# Sheet1.net
KiCad netlist of a schematic drawn in Altium Designer
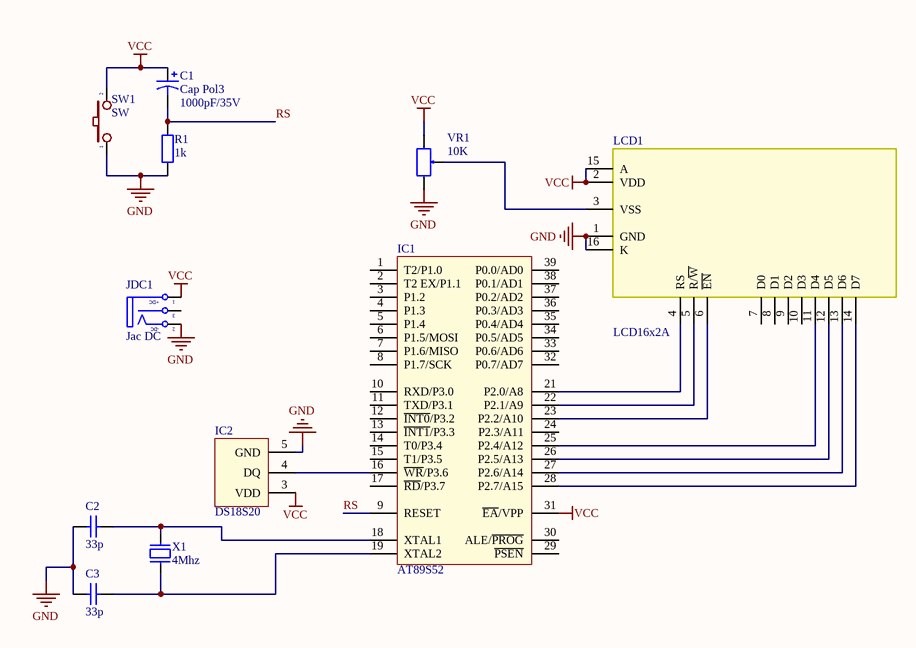
[diagram p0: Sheet1.SchDoc]

(export (version "E")
  (design (tool "Eeschema 10.0.6"))
  (components
    (comp (ref "C1")
      (value "Cap Pol3")
      (footprint "CP2/5")
      (description "Polarized Capacitor (Surface Mount)")
      (fields (field (name "ALTIUM_VALUE") "1000pF/35V") (field (name "PUBLISHER") "Altium Limited"))
      (libsource (lib "syhaunguyen") (part "Cap Pol3"))
    )
    (comp (ref "C2")
      (value "33p")
      (footprint "Tu-pico")
      (description "Capacitor")
      (fields (field (name "Comment") "Capacitor Ceramic") (field (name "PUBLISHER") "Altium Limited"))
      (libsource (lib "hphonglib") (part "CapCeramic"))
    )
    (comp (ref "C3")
      (value "33p")
      (footprint "Tu-pico")
      (description "Capacitor")
      (fields (field (name "Comment") "Capacitor Ceramic") (field (name "PUBLISHER") "Altium Limited"))
      (libsource (lib "hphonglib") (part "CapCeramic"))
    )
    (comp (ref "IC1")
      (value "AT89S52")
      (footprint "DIP40/W0.6")
      (description "AT89S52, 8k Byte Flash Memory , 40 Pin")
      (libsource (lib "syhaunguyen") (part "AT89S52"))
    )
    (comp (ref "IC2")
      (value "DS18S20")
      (footprint "DS18S20")
      (description "High Precision  1-Wire® Digital Thermometer")
      (libsource (lib "syhaunguyen") (part "DS18S20"))
    )
    (comp (ref "JDC1")
      (value "Jac DC")
      (footprint "DC-IN")
      (description "Jac DC input")
      (libsource (lib "syhaunguyen") (part "DCIN"))
    )
    (comp (ref "LCD1")
      (value "LCD16x2A")
      (footprint "LCD16X2")
      (description "LCD dipslay 16 char, 2 line")
      (libsource (lib "syhaunguyen") (part "LCD16x2"))
    )
    (comp (ref "R1")
      (value "1k")
      (footprint "R1/4W")
      (description "Resistor 1/4W")
      (libsource (lib "syhaunguyen") (part "R1/4W"))
    )
    (comp (ref "SW1")
      (value "SW")
      (footprint "SW2")
      (description "Switch button 2 pin")
      (libsource (lib "syhaunguyen") (part "SW2"))
    )
    (comp (ref "VR1")
      (value "10K")
      (footprint "VR")
      (description "Var Resistor")
      (libsource (lib "hphonglib") (part "VR"))
    )
    (comp (ref "X1")
      (value "4Mhz")
      (footprint "XT2")
      (description "Crystal For all Crystal 2pin.")
      (libsource (lib "hphonglib") (part "XT2"))
    )
  )
  (nets
    (net (code "1") (name "/RS") (class "Default")
      (node (ref "C1") (pin "2") (pinfunction "2_2") (pintype "passive"))
      (node (ref "IC1") (pin "9") (pinfunction "RESET_9") (pintype "passive"))
      (node (ref "R1") (pin "2") (pinfunction "2_2") (pintype "passive"))
    )
    (net (code "2") (name "GND") (class "Default")
      (node (ref "C2") (pin "1") (pinfunction "1_1") (pintype "passive"))
      (node (ref "C3") (pin "1") (pinfunction "1_1") (pintype "passive"))
      (node (ref "IC1") (pin "20") (pinfunction "GND_20") (pintype "power_in"))
      (node (ref "IC2") (pin "5") (pinfunction "GND_5") (pintype "passive"))
      (node (ref "JDC1") (pin "2") (pinfunction "TN_2") (pintype "passive"))
      (node (ref "LCD1") (pin "1") (pinfunction "GND_1") (pintype "passive"))
      (node (ref "LCD1") (pin "16") (pinfunction "K_16") (pintype "passive"))
      (node (ref "R1") (pin "1") (pinfunction "1_1") (pintype "passive"))
      (node (ref "SW1") (pin "1") (pinfunction "1_1") (pintype "passive"))
      (node (ref "VR1") (pin "3") (pinfunction "3_3") (pintype "passive"))
    )
    (net (code "3") (name "Net-(IC1-P2.0{slash}A8)") (class "Default")
      (node (ref "IC1") (pin "21") (pinfunction "P2.0/A8_21") (pintype "passive"))
      (node (ref "LCD1") (pin "4") (pinfunction "RS_4") (pintype "passive"))
    )
    (net (code "4") (name "Net-(IC1-P2.1{slash}A9)") (class "Default")
      (node (ref "IC1") (pin "22") (pinfunction "P2.1/A9_22") (pintype "passive"))
      (node (ref "LCD1") (pin "5") (pinfunction "R/~{W}_5") (pintype "passive"))
    )
    (net (code "5") (name "Net-(IC1-P2.2{slash}A10)") (class "Default")
      (node (ref "IC1") (pin "23") (pinfunction "P2.2/A10_23") (pintype "passive"))
      (node (ref "LCD1") (pin "6") (pinfunction "~{EN}_6") (pintype "passive"))
    )
    (net (code "6") (name "Net-(IC1-P2.4{slash}A12)") (class "Default")
      (node (ref "IC1") (pin "25") (pinfunction "P2.4/A12_25") (pintype "passive"))
      (node (ref "LCD1") (pin "11") (pinfunction "D4_11") (pintype "passive"))
    )
    (net (code "7") (name "Net-(IC1-P2.5{slash}A13)") (class "Default")
      (node (ref "IC1") (pin "26") (pinfunction "P2.5/A13_26") (pintype "passive"))
      (node (ref "LCD1") (pin "12") (pinfunction "D5_12") (pintype "passive"))
    )
    (net (code "8") (name "Net-(IC1-P2.6{slash}A14)") (class "Default")
      (node (ref "IC1") (pin "27") (pinfunction "P2.6/A14_27") (pintype "passive"))
      (node (ref "LCD1") (pin "13") (pinfunction "D6_13") (pintype "passive"))
    )
    (net (code "9") (name "Net-(IC1-P2.7{slash}A15)") (class "Default")
      (node (ref "IC1") (pin "28") (pinfunction "P2.7/A15_28") (pintype "passive"))
      (node (ref "LCD1") (pin "14") (pinfunction "D7_14") (pintype "passive"))
    )
    (net (code "10") (name "Net-(IC1-XTAL1)") (class "Default")
      (node (ref "C2") (pin "2") (pinfunction "2_2") (pintype "passive"))
      (node (ref "IC1") (pin "18") (pinfunction "XTAL1_18") (pintype "passive"))
      (node (ref "X1") (pin "1") (pinfunction "1_1") (pintype "passive"))
    )
    (net (code "11") (name "Net-(IC1-XTAL2)") (class "Default")
      (node (ref "C3") (pin "2") (pinfunction "2_2") (pintype "passive"))
      (node (ref "IC1") (pin "19") (pinfunction "XTAL2_19") (pintype "passive"))
      (node (ref "X1") (pin "2") (pinfunction "2_2") (pintype "passive"))
    )
    (net (code "12") (name "Net-(IC1-~{WR}{slash}P3.6)") (class "Default")
      (node (ref "IC1") (pin "16") (pinfunction "~{WR}/P3.6_16") (pintype "passive"))
      (node (ref "IC2") (pin "4") (pinfunction "DQ_4") (pintype "passive"))
    )
    (net (code "13") (name "Net-(LCD1-VSS)") (class "Default")
      (node (ref "LCD1") (pin "3") (pinfunction "VSS_3") (pintype "passive"))
      (node (ref "VR1") (pin "2") (pinfunction "2_2") (pintype "passive"))
    )
    (net (code "14") (name "VCC") (class "Default")
      (node (ref "C1") (pin "1") (pinfunction "1_1") (pintype "passive"))
      (node (ref "IC1") (pin "31") (pinfunction "~{EA}/VPP_31") (pintype "passive"))
      (node (ref "IC1") (pin "40") (pinfunction "VCC_40") (pintype "power_in"))
      (node (ref "IC2") (pin "3") (pinfunction "VDD_3") (pintype "passive"))
      (node (ref "JDC1") (pin "1") (pinfunction "T_1") (pintype "passive"))
      (node (ref "LCD1") (pin "15") (pinfunction "A_15") (pintype "passive"))
      (node (ref "LCD1") (pin "2") (pinfunction "VDD_2") (pintype "passive"))
      (node (ref "SW1") (pin "2") (pinfunction "2_2") (pintype "passive"))
      (node (ref "VR1") (pin "1") (pinfunction "1_1") (pintype "passive"))
    )
    (net (code "15") (name "unconnected-(IC1-ALE{slash}~{PROG}-Pad30)") (class "Default")
      (node (ref "IC1") (pin "30") (pinfunction "ALE/~{PROG}_30") (pintype "passive"))
    )
    (net (code "16") (name "unconnected-(IC1-P0.0{slash}AD0-Pad39)") (class "Default")
      (node (ref "IC1") (pin "39") (pinfunction "P0.0/AD0_39") (pintype "passive"))
    )
    (net (code "17") (name "unconnected-(IC1-P0.1{slash}AD1-Pad38)") (class "Default")
      (node (ref "IC1") (pin "38") (pinfunction "P0.1/AD1_38") (pintype "passive"))
    )
    (net (code "18") (name "unconnected-(IC1-P0.2{slash}AD2-Pad37)") (class "Default")
      (node (ref "IC1") (pin "37") (pinfunction "P0.2/AD2_37") (pintype "passive"))
    )
    (net (code "19") (name "unconnected-(IC1-P0.3{slash}AD3-Pad36)") (class "Default")
      (node (ref "IC1") (pin "36") (pinfunction "P0.3/AD3_36") (pintype "passive"))
    )
    (net (code "20") (name "unconnected-(IC1-P0.4{slash}AD4-Pad35)") (class "Default")
      (node (ref "IC1") (pin "35") (pinfunction "P0.4/AD4_35") (pintype "passive"))
    )
    (net (code "21") (name "unconnected-(IC1-P0.5{slash}AD5-Pad34)") (class "Default")
      (node (ref "IC1") (pin "34") (pinfunction "P0.5/AD5_34") (pintype "passive"))
    )
    (net (code "22") (name "unconnected-(IC1-P0.6{slash}AD6-Pad33)") (class "Default")
      (node (ref "IC1") (pin "33") (pinfunction "P0.6/AD6_33") (pintype "passive"))
    )
    (net (code "23") (name "unconnected-(IC1-P0.7{slash}AD7-Pad32)") (class "Default")
      (node (ref "IC1") (pin "32") (pinfunction "P0.7/AD7_32") (pintype "passive"))
    )
    (net (code "24") (name "unconnected-(IC1-P1.2-Pad3)") (class "Default")
      (node (ref "IC1") (pin "3") (pinfunction "P1.2_3") (pintype "passive"))
    )
    (net (code "25") (name "unconnected-(IC1-P1.3-Pad4)") (class "Default")
      (node (ref "IC1") (pin "4") (pinfunction "P1.3_4") (pintype "passive"))
    )
    (net (code "26") (name "unconnected-(IC1-P1.4-Pad5)") (class "Default")
      (node (ref "IC1") (pin "5") (pinfunction "P1.4_5") (pintype "passive"))
    )
    (net (code "27") (name "unconnected-(IC1-P1.5{slash}MOSI-Pad6)") (class "Default")
      (node (ref "IC1") (pin "6") (pinfunction "P1.5/MOSI_6") (pintype "passive"))
    )
    (net (code "28") (name "unconnected-(IC1-P1.6{slash}MISO-Pad7)") (class "Default")
      (node (ref "IC1") (pin "7") (pinfunction "P1.6/MISO_7") (pintype "passive"))
    )
    (net (code "29") (name "unconnected-(IC1-P1.7{slash}SCK-Pad8)") (class "Default")
      (node (ref "IC1") (pin "8") (pinfunction "P1.7/SCK_8") (pintype "passive"))
    )
    (net (code "30") (name "unconnected-(IC1-P2.3{slash}A11-Pad24)") (class "Default")
      (node (ref "IC1") (pin "24") (pinfunction "P2.3/A11_24") (pintype "passive"))
    )
    (net (code "31") (name "unconnected-(IC1-RXD{slash}P3.0-Pad10)") (class "Default")
      (node (ref "IC1") (pin "10") (pinfunction "RXD/P3.0_10") (pintype "passive"))
    )
    (net (code "32") (name "unconnected-(IC1-T0{slash}P3.4-Pad14)") (class "Default")
      (node (ref "IC1") (pin "14") (pinfunction "T0/P3.4_14") (pintype "passive"))
    )
    (net (code "33") (name "unconnected-(IC1-T1{slash}P3.5-Pad15)") (class "Default")
      (node (ref "IC1") (pin "15") (pinfunction "T1/P3.5_15") (pintype "passive"))
    )
    (net (code "34") (name "unconnected-(IC1-T2_EX{slash}P1.1-Pad2)") (class "Default")
      (node (ref "IC1") (pin "2") (pinfunction "T2_EX/P1.1_2") (pintype "passive"))
    )
    (net (code "35") (name "unconnected-(IC1-T2{slash}P1.0-Pad1)") (class "Default")
      (node (ref "IC1") (pin "1") (pinfunction "T2/P1.0_1") (pintype "passive"))
    )
    (net (code "36") (name "unconnected-(IC1-TXD{slash}P3.1-Pad11)") (class "Default")
      (node (ref "IC1") (pin "11") (pinfunction "TXD/P3.1_11") (pintype "passive"))
    )
    (net (code "37") (name "unconnected-(IC1-~{INT0}{slash}P3.2-Pad12)") (class "Default")
      (node (ref "IC1") (pin "12") (pinfunction "~{INT0}/P3.2_12") (pintype "passive"))
    )
    (net (code "38") (name "unconnected-(IC1-~{INT1}{slash}P3.3-Pad13)") (class "Default")
      (node (ref "IC1") (pin "13") (pinfunction "~{INT1}/P3.3_13") (pintype "passive"))
    )
    (net (code "39") (name "unconnected-(IC1-~{PSEN}-Pad29)") (class "Default")
      (node (ref "IC1") (pin "29") (pinfunction "~{PSEN}_29") (pintype "passive"))
    )
    (net (code "40") (name "unconnected-(IC1-~{RD}{slash}P3.7-Pad17)") (class "Default")
      (node (ref "IC1") (pin "17") (pinfunction "~{RD}/P3.7_17") (pintype "passive"))
    )
    (net (code "41") (name "unconnected-(JDC1-S-Pad3)") (class "Default")
      (node (ref "JDC1") (pin "3") (pinfunction "S_3") (pintype "power_in"))
    )
    (net (code "42") (name "unconnected-(LCD1-D0-Pad7)") (class "Default")
      (node (ref "LCD1") (pin "7") (pinfunction "D0_7") (pintype "passive"))
    )
    (net (code "43") (name "unconnected-(LCD1-D1-Pad8)") (class "Default")
      (node (ref "LCD1") (pin "8") (pinfunction "D1_8") (pintype "passive"))
    )
    (net (code "44") (name "unconnected-(LCD1-D2-Pad9)") (class "Default")
      (node (ref "LCD1") (pin "9") (pinfunction "D2_9") (pintype "passive"))
    )
    (net (code "45") (name "unconnected-(LCD1-D3-Pad10)") (class "Default")
      (node (ref "LCD1") (pin "10") (pinfunction "D3_10") (pintype "passive"))
    )
  )
)
